# DPPXHK_FMUPOWER.net
KiCad netlist of a schematic drawn in Altium Designer
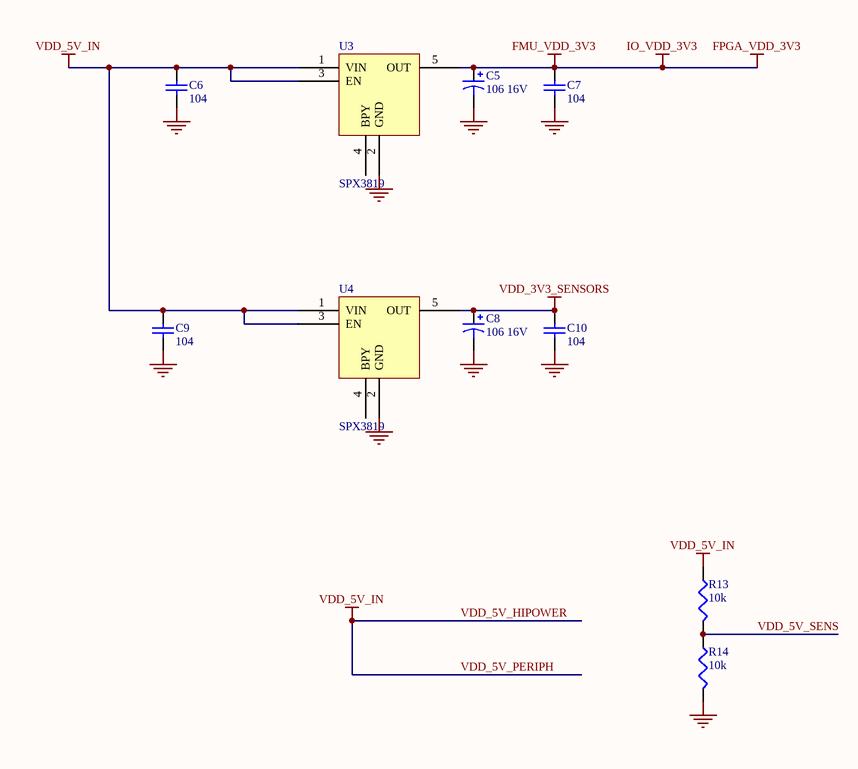
[diagram p0: DPPXHK_FMUPOWER.SCHDOC]

(export (version "E")
  (design (tool "Eeschema 10.0.6"))
  (components
    (comp (ref "C5")
      (value "106 16V")
      (footprint "LC0402")
      (description "Polarized Capacitor (Surface Mount)")
      (fields (field (name "PUBLISHER") "Altium Limited"))
      (libsource (lib "Miscellaneous Devices") (part "Cap Pol3"))
    )
    (comp (ref "C6")
      (value "104")
      (footprint "LC0402")
      (description "Capacitor (Semiconductor SIM Model)")
      (fields (field (name "PUBLISHER") "Altium Limited"))
      (libsource (lib "Miscellaneous Devices") (part "Cap Semi"))
    )
    (comp (ref "C7")
      (value "104")
      (footprint "LC0402")
      (description "Capacitor (Semiconductor SIM Model)")
      (fields (field (name "PUBLISHER") "Altium Limited"))
      (libsource (lib "Miscellaneous Devices") (part "Cap Semi"))
    )
    (comp (ref "C8")
      (value "106 16V")
      (footprint "LC0402")
      (description "Polarized Capacitor (Surface Mount)")
      (fields (field (name "PUBLISHER") "Altium Limited"))
      (libsource (lib "Miscellaneous Devices") (part "Cap Pol3"))
    )
    (comp (ref "C9")
      (value "104")
      (footprint "LC0402")
      (description "Capacitor (Semiconductor SIM Model)")
      (fields (field (name "PUBLISHER") "Altium Limited"))
      (libsource (lib "Miscellaneous Devices") (part "Cap Semi"))
    )
    (comp (ref "C10")
      (value "104")
      (footprint "LC0402")
      (description "Capacitor (Semiconductor SIM Model)")
      (fields (field (name "PUBLISHER") "Altium Limited"))
      (libsource (lib "Miscellaneous Devices") (part "Cap Semi"))
    )
    (comp (ref "R13")
      (value "10k")
      (footprint "0402R")
      (description "Resistor")
      (fields (field (name "PUBLISHER") "Altium Limited"))
      (libsource (lib "Miscellaneous Devices") (part "Res3"))
    )
    (comp (ref "R14")
      (value "10k")
      (footprint "0402R")
      (description "Resistor")
      (fields (field (name "PUBLISHER") "Altium Limited"))
      (libsource (lib "Miscellaneous Devices") (part "Res3"))
    )
    (comp (ref "U3") (value "SPX3819") (footprint "SOT-23-5") (libsource (lib "PXHK") (part "SPX3819")))
    (comp (ref "U4") (value "SPX3819") (footprint "SOT-23-5") (libsource (lib "PXHK") (part "SPX3819")))
  )
  (nets
    (net (code "1") (name "/VDD_5V_SENS") (class "Default")
      (node (ref "R13") (pin "2") (pinfunction "2_2") (pintype "passive"))
      (node (ref "R14") (pin "1") (pinfunction "1_1") (pintype "passive"))
    )
    (net (code "2") (name "FMU_VDD_3V3") (class "Default")
      (node (ref "C5") (pin "1") (pinfunction "1_1") (pintype "passive"))
      (node (ref "C7") (pin "2") (pinfunction "2_2") (pintype "passive"))
      (node (ref "U3") (pin "5") (pinfunction "OUT_5") (pintype "passive"))
    )
    (net (code "3") (name "GND") (class "Default")
      (node (ref "C10") (pin "1") (pinfunction "1_1") (pintype "passive"))
      (node (ref "C5") (pin "2") (pinfunction "2_2") (pintype "passive"))
      (node (ref "C6") (pin "1") (pinfunction "1_1") (pintype "passive"))
      (node (ref "C7") (pin "1") (pinfunction "1_1") (pintype "passive"))
      (node (ref "C8") (pin "2") (pinfunction "2_2") (pintype "passive"))
      (node (ref "C9") (pin "1") (pinfunction "1_1") (pintype "passive"))
      (node (ref "R14") (pin "2") (pinfunction "2_2") (pintype "passive"))
      (node (ref "U3") (pin "2") (pinfunction "GND_2") (pintype "passive"))
      (node (ref "U4") (pin "2") (pinfunction "GND_2") (pintype "passive"))
    )
    (net (code "4") (name "VDD_3V3_SENSORS") (class "Default")
      (node (ref "C10") (pin "2") (pinfunction "2_2") (pintype "passive"))
      (node (ref "C8") (pin "1") (pinfunction "1_1") (pintype "passive"))
      (node (ref "U4") (pin "5") (pinfunction "OUT_5") (pintype "passive"))
    )
    (net (code "5") (name "VDD_5V_IN") (class "Default")
      (node (ref "C6") (pin "2") (pinfunction "2_2") (pintype "passive"))
      (node (ref "C9") (pin "2") (pinfunction "2_2") (pintype "passive"))
      (node (ref "R13") (pin "1") (pinfunction "1_1") (pintype "passive"))
      (node (ref "U3") (pin "1") (pinfunction "VIN_1") (pintype "passive"))
      (node (ref "U3") (pin "3") (pinfunction "EN_3") (pintype "passive"))
      (node (ref "U4") (pin "1") (pinfunction "VIN_1") (pintype "passive"))
      (node (ref "U4") (pin "3") (pinfunction "EN_3") (pintype "passive"))
    )
    (net (code "6") (name "unconnected-(U3-BPY-Pad4)") (class "Default")
      (node (ref "U3") (pin "4") (pinfunction "BPY_4") (pintype "passive"))
    )
    (net (code "7") (name "unconnected-(U4-BPY-Pad4)") (class "Default")
      (node (ref "U4") (pin "4") (pinfunction "BPY_4") (pintype "passive"))
    )
  )
)
